# BottomPCB-011713.net
KiCad netlist of a schematic drawn in EAGLE
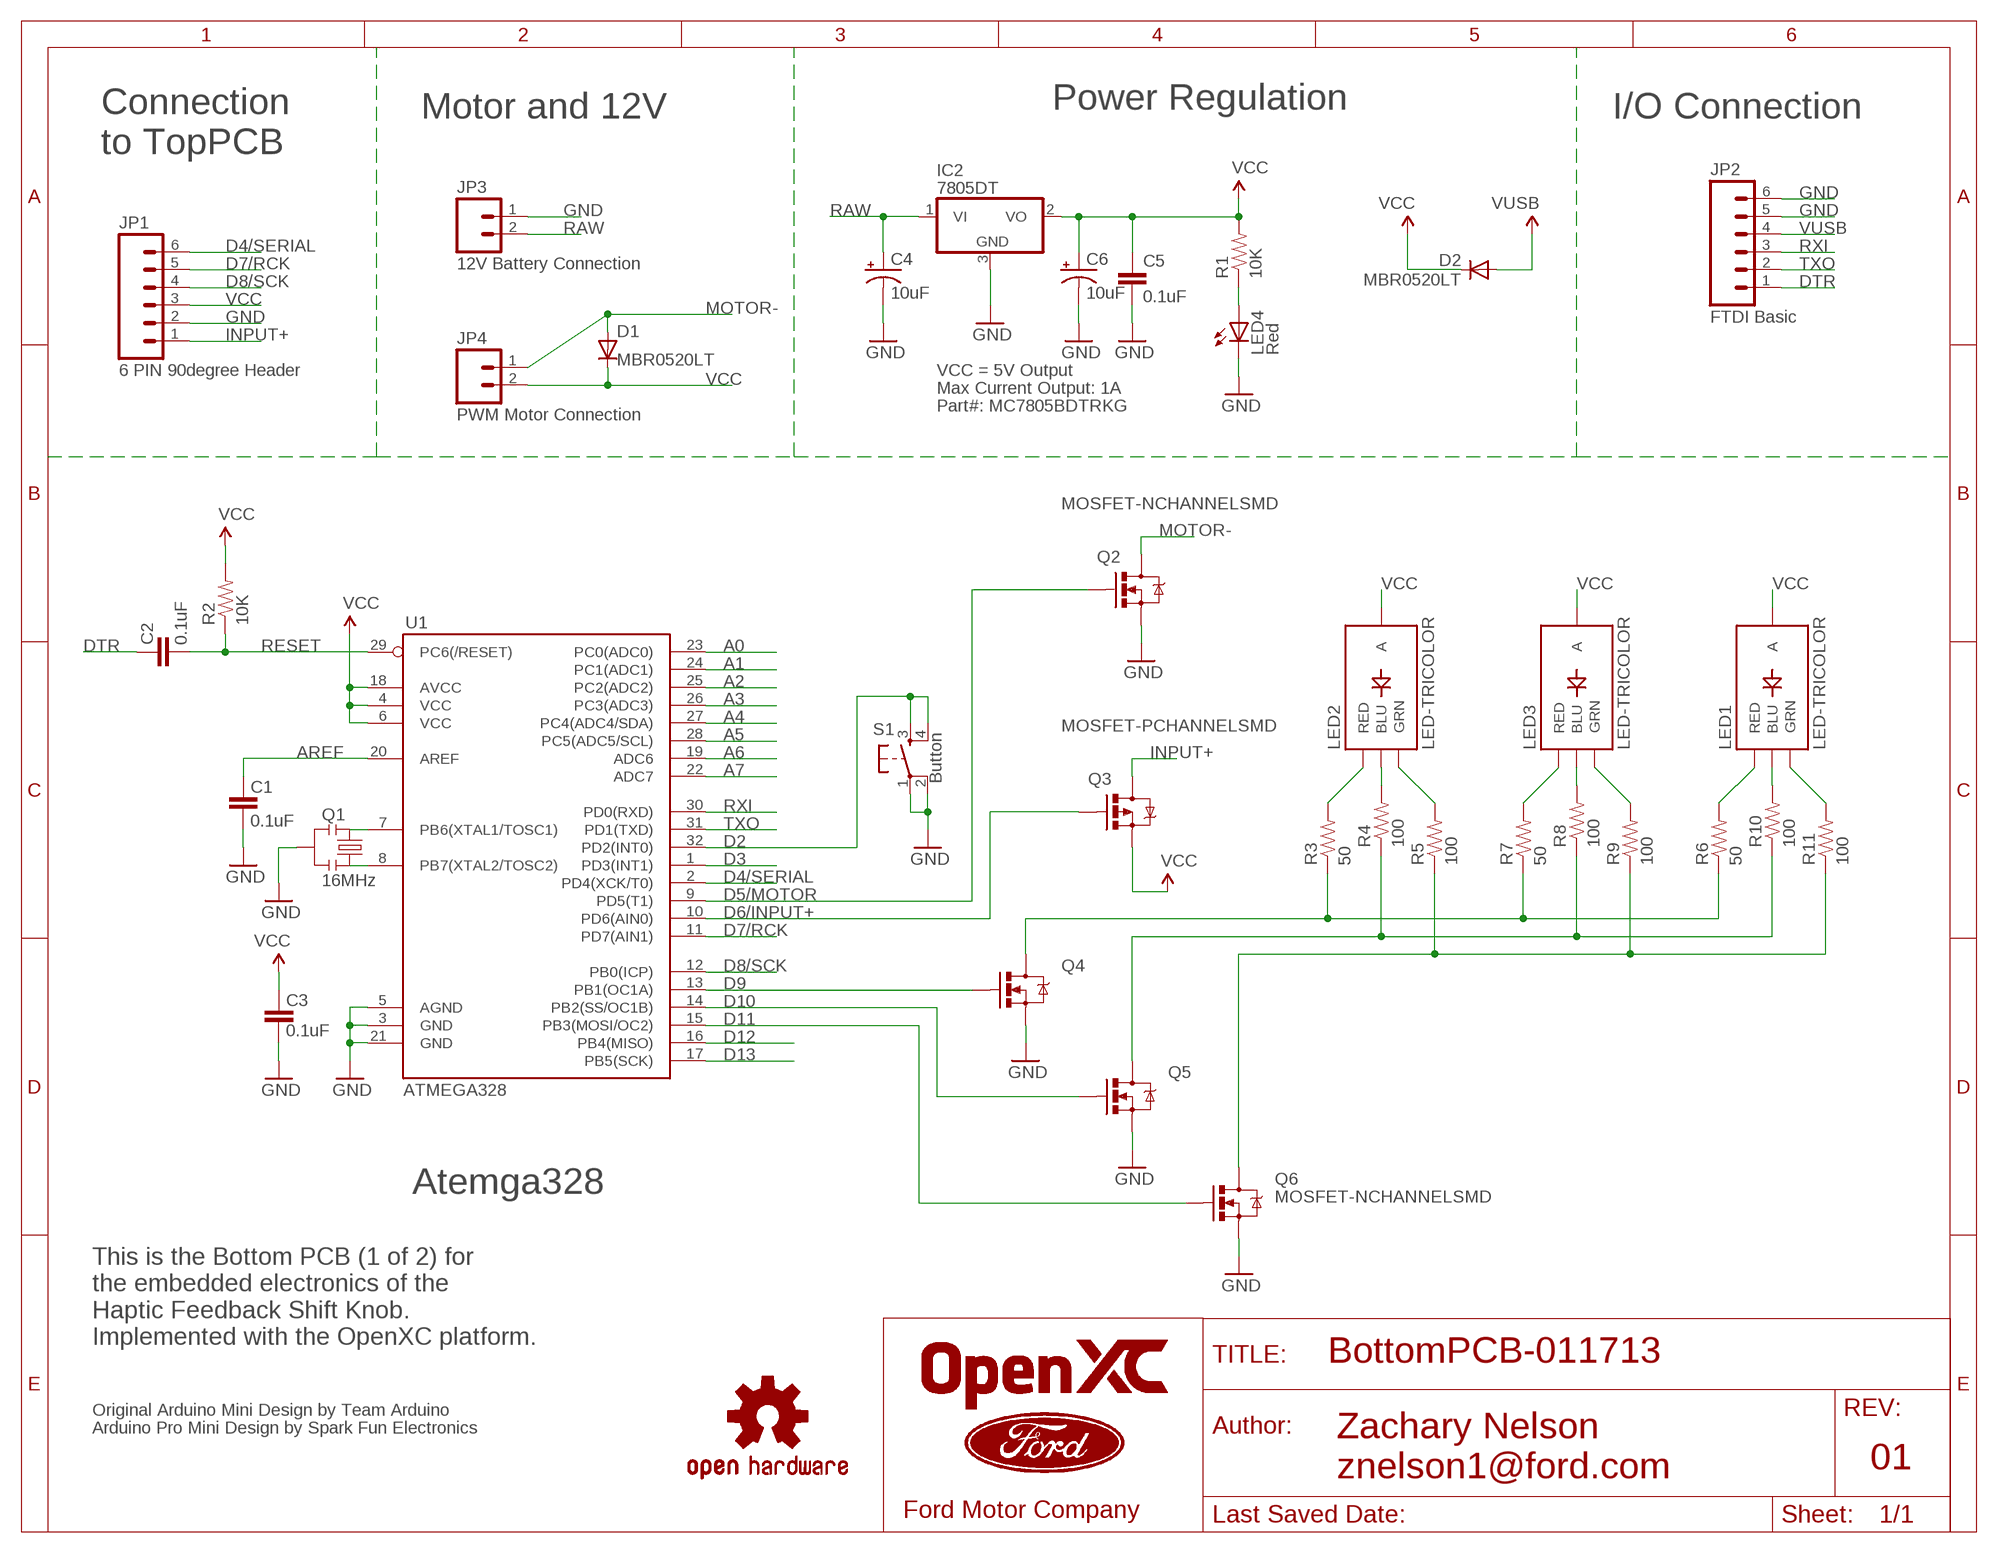
[diagram p0: schematic, sheet 1]

(export (version "E")
  (design (tool "Eeschema 10.0.6"))
  (components
    (comp (ref "C1")
      (value "0.1uF")
      (footprint "eagle-import:0402-CAP")
      (libsource (lib "eagle-import") (part "CAP0402-CAP"))
    )
    (comp (ref "C2")
      (value "0.1uF")
      (footprint "eagle-import:0402-CAP")
      (libsource (lib "eagle-import") (part "CAP0402-CAP"))
    )
    (comp (ref "C3")
      (value "0.1uF")
      (footprint "eagle-import:0402-CAP")
      (libsource (lib "eagle-import") (part "CAP0402-CAP"))
    )
    (comp (ref "C4")
      (value "10uF")
      (footprint "eagle-import:EIA3216")
      (libsource (lib "eagle-import") (part "CAP_POL1206"))
    )
    (comp (ref "C5")
      (value "0.1uF")
      (footprint "eagle-import:0402-CAP")
      (libsource (lib "eagle-import") (part "CAP0402-CAP"))
    )
    (comp (ref "C6")
      (value "10uF")
      (footprint "eagle-import:EIA3216")
      (libsource (lib "eagle-import") (part "CAP_POL1206"))
    )
    (comp (ref "D1")
      (value "MBR0520LT")
      (footprint "eagle-import:SOD123")
      (libsource (lib "eagle-import") (part "MBR0520LT"))
    )
    (comp (ref "D2")
      (value "MBR0520LT")
      (footprint "eagle-import:SOD123")
      (libsource (lib "eagle-import") (part "MBR0520LT"))
    )
    (comp (ref "IC2")
      (value "7805DT")
      (footprint "eagle-import:TO252")
      (libsource (lib "eagle-import") (part "78DT05"))
    )
    (comp (ref "JP1")
      (value "6 PIN 90degree Header")
      (footprint "eagle-import:1X06")
      (libsource (lib "eagle-import") (part "M06SIP"))
    )
    (comp (ref "JP2")
      (value "FTDI Basic")
      (footprint "eagle-import:1X06")
      (libsource (lib "eagle-import") (part "M06SIP"))
    )
    (comp (ref "JP3")
      (value "12V Battery Connection")
      (footprint "eagle-import:JST-2-SMD")
      (fields (field (name "PROD_ID") "CONN-08352"))
      (libsource (lib "eagle-import") (part "M02-JST-2MM-SMT"))
    )
    (comp (ref "JP4")
      (value "PWM Motor Connection")
      (footprint "eagle-import:JST-2-SMD")
      (libsource (lib "eagle-import") (part "M02-JST-2MM-SMT"))
    )
    (comp (ref "LED1")
      (value "LED-TRICOLOR")
      (footprint "eagle-import:LED-TRICOLOR-SMD")
      (libsource (lib "eagle-import") (part "LED-TRICOLOR"))
    )
    (comp (ref "LED2")
      (value "LED-TRICOLOR")
      (footprint "eagle-import:LED-TRICOLOR-SMD")
      (libsource (lib "eagle-import") (part "LED-TRICOLOR"))
    )
    (comp (ref "LED3")
      (value "LED-TRICOLOR")
      (footprint "eagle-import:LED-TRICOLOR-SMD")
      (libsource (lib "eagle-import") (part "LED-TRICOLOR"))
    )
    (comp (ref "LED4")
      (value "Red")
      (footprint "eagle-import:LED-0603")
      (libsource (lib "eagle-import") (part "LED0603"))
    )
    (comp (ref "Q1")
      (value "16MHz")
      (footprint "eagle-import:RESONATOR-SMD")
      (libsource (lib "eagle-import") (part "RESONATORSMD"))
    )
    (comp (ref "Q2")
      (value "MOSFET-NCHANNELSMD")
      (footprint "eagle-import:SOT23-3")
      (libsource (lib "eagle-import") (part "MOSFET-NCHANNELSMD"))
    )
    (comp (ref "Q3")
      (value "MOSFET-PCHANNELSMD")
      (footprint "eagle-import:SOT23-3")
      (libsource (lib "eagle-import") (part "MOSFET-PCHANNELSMD"))
    )
    (comp (ref "Q4")
      (value "MOSFET-NCHANNELSMD")
      (footprint "eagle-import:SOT23-3")
      (libsource (lib "eagle-import") (part "MOSFET-NCHANNELSMD"))
    )
    (comp (ref "Q5")
      (value "MOSFET-NCHANNELSMD")
      (footprint "eagle-import:SOT23-3")
      (libsource (lib "eagle-import") (part "MOSFET-NCHANNELSMD"))
    )
    (comp (ref "Q6")
      (value "MOSFET-NCHANNELSMD")
      (footprint "eagle-import:SOT23-3")
      (libsource (lib "eagle-import") (part "MOSFET-NCHANNELSMD"))
    )
    (comp (ref "R1")
      (value "10K")
      (footprint "eagle-import:0402-RES")
      (libsource (lib "eagle-import") (part "RESISTOR0402-RES"))
    )
    (comp (ref "R2")
      (value "10K")
      (footprint "eagle-import:0402-RES")
      (libsource (lib "eagle-import") (part "RESISTOR0402-RES"))
    )
    (comp (ref "R3")
      (value "50")
      (footprint "eagle-import:0805")
      (libsource (lib "eagle-import") (part "SparkFun-Resistors_RESISTOR0805-RES"))
    )
    (comp (ref "R4")
      (value "100")
      (footprint "eagle-import:0805")
      (libsource (lib "eagle-import") (part "SparkFun-Resistors_RESISTOR0805-RES"))
    )
    (comp (ref "R5")
      (value "100")
      (footprint "eagle-import:0805")
      (libsource (lib "eagle-import") (part "SparkFun-Resistors_RESISTOR0805-RES"))
    )
    (comp (ref "R6")
      (value "50")
      (footprint "eagle-import:0805")
      (libsource (lib "eagle-import") (part "SparkFun-Resistors_RESISTOR0805-RES"))
    )
    (comp (ref "R7")
      (value "50")
      (footprint "eagle-import:0805")
      (libsource (lib "eagle-import") (part "SparkFun-Resistors_RESISTOR0805-RES"))
    )
    (comp (ref "R8")
      (value "100")
      (footprint "eagle-import:0805")
      (libsource (lib "eagle-import") (part "SparkFun-Resistors_RESISTOR0805-RES"))
    )
    (comp (ref "R9")
      (value "100")
      (footprint "eagle-import:0805")
      (libsource (lib "eagle-import") (part "SparkFun-Resistors_RESISTOR0805-RES"))
    )
    (comp (ref "R10")
      (value "100")
      (footprint "eagle-import:0805")
      (libsource (lib "eagle-import") (part "SparkFun-Resistors_RESISTOR0805-RES"))
    )
    (comp (ref "R11")
      (value "100")
      (footprint "eagle-import:0805")
      (libsource (lib "eagle-import") (part "SparkFun-Resistors_RESISTOR0805-RES"))
    )
    (comp (ref "S1")
      (value "Button")
      (footprint "eagle-import:TACTILE_SWITCH_SMD")
      (libsource (lib "eagle-import") (part "TAC_SWITCHSMD"))
    )
    (comp (ref "U$3")
      (value "OSHW-LOGOS")
      (footprint "eagle-import:OSHW-LOGO-S")
      (libsource (lib "eagle-import") (part "OSHW-LOGOS"))
    )
    (comp (ref "U1")
      (value "ATMEGA328")
      (footprint "eagle-import:TQFP32-08")
      (libsource (lib "eagle-import") (part "ATMEGA168"))
    )
  )
  (nets
    (net (code "1") (name "/A0") (class "Default")
      (node (ref "U1") (pin "23") (pinfunction "PC0(ADC0)_23") (pintype "bidirectional"))
    )
    (net (code "2") (name "/A1") (class "Default")
      (node (ref "U1") (pin "24") (pinfunction "PC1(ADC1)_24") (pintype "bidirectional"))
    )
    (net (code "3") (name "/A2") (class "Default")
      (node (ref "U1") (pin "25") (pinfunction "PC2(ADC2)_25") (pintype "bidirectional"))
    )
    (net (code "4") (name "/A3") (class "Default")
      (node (ref "U1") (pin "26") (pinfunction "PC3(ADC3)_26") (pintype "bidirectional"))
    )
    (net (code "5") (name "/A4") (class "Default")
      (node (ref "U1") (pin "27") (pinfunction "PC4(ADC4/SDA)_27") (pintype "bidirectional"))
    )
    (net (code "6") (name "/A5") (class "Default")
      (node (ref "U1") (pin "28") (pinfunction "PC5(ADC5/SCL)_28") (pintype "bidirectional"))
    )
    (net (code "7") (name "/A6") (class "Default")
      (node (ref "U1") (pin "19") (pinfunction "ADC6_19") (pintype "bidirectional"))
    )
    (net (code "8") (name "/A7") (class "Default")
      (node (ref "U1") (pin "22") (pinfunction "ADC7_22") (pintype "bidirectional"))
    )
    (net (code "9") (name "/AREF") (class "Default")
      (node (ref "C1") (pin "2") (pinfunction "2_2") (pintype "passive"))
      (node (ref "U1") (pin "20") (pinfunction "AREF_20") (pintype "bidirectional"))
    )
    (net (code "10") (name "/D2") (class "Default")
      (node (ref "S1") (pin "3") (pinfunction "3_3") (pintype "passive"))
      (node (ref "S1") (pin "4") (pinfunction "4_4") (pintype "passive"))
      (node (ref "U1") (pin "32") (pinfunction "PD2(INT0)_32") (pintype "bidirectional"))
    )
    (net (code "11") (name "/D3") (class "Default")
      (node (ref "U1") (pin "1") (pinfunction "PD3(INT1)_1") (pintype "bidirectional"))
    )
    (net (code "12") (name "/D4{slash}SERIAL") (class "Default")
      (node (ref "JP1") (pin "6") (pinfunction "6_6") (pintype "passive"))
      (node (ref "U1") (pin "2") (pinfunction "PD4(XCK/T0)_2") (pintype "bidirectional"))
    )
    (net (code "13") (name "/D5{slash}MOTOR") (class "Default")
      (node (ref "Q2") (pin "1") (pinfunction "G_1") (pintype "passive"))
      (node (ref "U1") (pin "9") (pinfunction "PD5(T1)_9") (pintype "bidirectional"))
    )
    (net (code "14") (name "/D6{slash}INPUT+") (class "Default")
      (node (ref "Q3") (pin "1") (pinfunction "G_1") (pintype "passive"))
      (node (ref "U1") (pin "10") (pinfunction "PD6(AIN0)_10") (pintype "bidirectional"))
    )
    (net (code "15") (name "/D7{slash}RCK") (class "Default")
      (node (ref "JP1") (pin "5") (pinfunction "5_5") (pintype "passive"))
      (node (ref "U1") (pin "11") (pinfunction "PD7(AIN1)_11") (pintype "bidirectional"))
    )
    (net (code "16") (name "/D8{slash}SCK") (class "Default")
      (node (ref "JP1") (pin "4") (pinfunction "4_4") (pintype "passive"))
      (node (ref "U1") (pin "12") (pinfunction "PB0(ICP)_12") (pintype "bidirectional"))
    )
    (net (code "17") (name "/D9") (class "Default")
      (node (ref "Q4") (pin "3") (pinfunction "D_3") (pintype "passive"))
      (node (ref "R3") (pin "1") (pinfunction "1_1") (pintype "passive"))
      (node (ref "R6") (pin "1") (pinfunction "1_1") (pintype "passive"))
      (node (ref "R7") (pin "1") (pinfunction "1_1") (pintype "passive"))
    )
    (net (code "18") (name "/D10") (class "Default")
      (node (ref "Q5") (pin "3") (pinfunction "D_3") (pintype "passive"))
      (node (ref "R10") (pin "1") (pinfunction "1_1") (pintype "passive"))
      (node (ref "R4") (pin "1") (pinfunction "1_1") (pintype "passive"))
      (node (ref "R8") (pin "1") (pinfunction "1_1") (pintype "passive"))
    )
    (net (code "19") (name "/D11") (class "Default")
      (node (ref "Q6") (pin "3") (pinfunction "D_3") (pintype "passive"))
      (node (ref "R11") (pin "1") (pinfunction "1_1") (pintype "passive"))
      (node (ref "R5") (pin "1") (pinfunction "1_1") (pintype "passive"))
      (node (ref "R9") (pin "1") (pinfunction "1_1") (pintype "passive"))
    )
    (net (code "20") (name "/D12") (class "Default")
      (node (ref "U1") (pin "16") (pinfunction "PB4(MISO)_16") (pintype "bidirectional"))
    )
    (net (code "21") (name "/D13") (class "Default")
      (node (ref "U1") (pin "17") (pinfunction "PB5(SCK)_17") (pintype "bidirectional"))
    )
    (net (code "22") (name "/DTR") (class "Default")
      (node (ref "C2") (pin "2") (pinfunction "2_2") (pintype "passive"))
      (node (ref "JP2") (pin "1") (pinfunction "1_1") (pintype "passive"))
    )
    (net (code "23") (name "/INPUT+") (class "Default")
      (node (ref "JP1") (pin "1") (pinfunction "1_1") (pintype "passive"))
      (node (ref "Q3") (pin "3") (pinfunction "D_3") (pintype "passive"))
    )
    (net (code "24") (name "/MOTOR-") (class "Default")
      (node (ref "D1") (pin "A") (pinfunction "A_A") (pintype "passive"))
      (node (ref "JP4") (pin "1") (pinfunction "2_1") (pintype "passive"))
      (node (ref "Q2") (pin "3") (pinfunction "D_3") (pintype "passive"))
    )
    (net (code "25") (name "/RAW") (class "Default")
      (node (ref "C4") (pin "A") (pinfunction "+_A") (pintype "passive"))
      (node (ref "IC2") (pin "1") (pinfunction "VI_1") (pintype "input"))
      (node (ref "JP3") (pin "2") (pinfunction "1_2") (pintype "passive"))
    )
    (net (code "26") (name "/RESET") (class "Default")
      (node (ref "C2") (pin "1") (pinfunction "1_1") (pintype "passive"))
      (node (ref "R2") (pin "1") (pinfunction "1_1") (pintype "passive"))
      (node (ref "U1") (pin "29") (pinfunction "PC6(/RESET)_29") (pintype "bidirectional"))
    )
    (net (code "27") (name "/RXI") (class "Default")
      (node (ref "JP2") (pin "3") (pinfunction "3_3") (pintype "passive"))
      (node (ref "U1") (pin "30") (pinfunction "PD0(RXD)_30") (pintype "bidirectional"))
    )
    (net (code "28") (name "/TXO") (class "Default")
      (node (ref "JP2") (pin "2") (pinfunction "2_2") (pintype "passive"))
      (node (ref "U1") (pin "31") (pinfunction "PD1(TXD)_31") (pintype "bidirectional"))
    )
    (net (code "29") (name "GND") (class "Default")
      (node (ref "C1") (pin "1") (pinfunction "1_1") (pintype "passive"))
      (node (ref "C3") (pin "1") (pinfunction "1_1") (pintype "passive"))
      (node (ref "C4") (pin "C") (pinfunction "-_C") (pintype "passive"))
      (node (ref "C5") (pin "2") (pinfunction "2_2") (pintype "passive"))
      (node (ref "C6") (pin "C") (pinfunction "-_C") (pintype "passive"))
      (node (ref "IC2") (pin "3") (pinfunction "GND_3") (pintype "passive"))
      (node (ref "JP1") (pin "2") (pinfunction "2_2") (pintype "passive"))
      (node (ref "JP2") (pin "5") (pinfunction "5_5") (pintype "passive"))
      (node (ref "JP2") (pin "6") (pinfunction "6_6") (pintype "passive"))
      (node (ref "JP3") (pin "1") (pinfunction "2_1") (pintype "passive"))
      (node (ref "LED4") (pin "C") (pinfunction "C_C") (pintype "passive"))
      (node (ref "Q1") (pin "2") (pinfunction "2_2") (pintype "passive"))
      (node (ref "Q2") (pin "2") (pinfunction "S_2") (pintype "passive"))
      (node (ref "Q4") (pin "2") (pinfunction "S_2") (pintype "passive"))
      (node (ref "Q5") (pin "2") (pinfunction "S_2") (pintype "passive"))
      (node (ref "Q6") (pin "2") (pinfunction "S_2") (pintype "passive"))
      (node (ref "S1") (pin "1") (pinfunction "1_1") (pintype "passive"))
      (node (ref "S1") (pin "2") (pinfunction "2_2") (pintype "passive"))
      (node (ref "U1") (pin "21") (pinfunction "GND_21") (pintype "bidirectional"))
      (node (ref "U1") (pin "3") (pinfunction "GND_3") (pintype "bidirectional"))
      (node (ref "U1") (pin "5") (pinfunction "AGND_5") (pintype "bidirectional"))
    )
    (net (code "30") (name "Net-(LED1-BLU)") (class "Default")
      (node (ref "LED1") (pin "B") (pinfunction "BLU_B") (pintype "bidirectional"))
      (node (ref "R10") (pin "2") (pinfunction "2_2") (pintype "passive"))
    )
    (net (code "31") (name "Net-(LED1-GRN)") (class "Default")
      (node (ref "LED1") (pin "G") (pinfunction "GRN_G") (pintype "bidirectional"))
      (node (ref "R11") (pin "2") (pinfunction "2_2") (pintype "passive"))
    )
    (net (code "32") (name "Net-(LED1-RED)") (class "Default")
      (node (ref "LED1") (pin "R") (pinfunction "RED_R") (pintype "bidirectional"))
      (node (ref "R6") (pin "2") (pinfunction "2_2") (pintype "passive"))
    )
    (net (code "33") (name "Net-(LED2-BLU)") (class "Default")
      (node (ref "LED2") (pin "B") (pinfunction "BLU_B") (pintype "bidirectional"))
      (node (ref "R4") (pin "2") (pinfunction "2_2") (pintype "passive"))
    )
    (net (code "34") (name "Net-(LED2-GRN)") (class "Default")
      (node (ref "LED2") (pin "G") (pinfunction "GRN_G") (pintype "bidirectional"))
      (node (ref "R5") (pin "2") (pinfunction "2_2") (pintype "passive"))
    )
    (net (code "35") (name "Net-(LED2-RED)") (class "Default")
      (node (ref "LED2") (pin "R") (pinfunction "RED_R") (pintype "bidirectional"))
      (node (ref "R3") (pin "2") (pinfunction "2_2") (pintype "passive"))
    )
    (net (code "36") (name "Net-(LED3-BLU)") (class "Default")
      (node (ref "LED3") (pin "B") (pinfunction "BLU_B") (pintype "bidirectional"))
      (node (ref "R8") (pin "2") (pinfunction "2_2") (pintype "passive"))
    )
    (net (code "37") (name "Net-(LED3-GRN)") (class "Default")
      (node (ref "LED3") (pin "G") (pinfunction "GRN_G") (pintype "bidirectional"))
      (node (ref "R9") (pin "2") (pinfunction "2_2") (pintype "passive"))
    )
    (net (code "38") (name "Net-(LED3-RED)") (class "Default")
      (node (ref "LED3") (pin "R") (pinfunction "RED_R") (pintype "bidirectional"))
      (node (ref "R7") (pin "2") (pinfunction "2_2") (pintype "passive"))
    )
    (net (code "39") (name "Net-(LED4-PadA)") (class "Default")
      (node (ref "LED4") (pin "A") (pinfunction "A_A") (pintype "passive"))
      (node (ref "R1") (pin "1") (pinfunction "1_1") (pintype "passive"))
    )
    (net (code "40") (name "Net-(Q4-G)") (class "Default")
      (node (ref "Q4") (pin "1") (pinfunction "G_1") (pintype "passive"))
      (node (ref "U1") (pin "13") (pinfunction "PB1(OC1A)_13") (pintype "bidirectional"))
    )
    (net (code "41") (name "Net-(Q5-G)") (class "Default")
      (node (ref "Q5") (pin "1") (pinfunction "G_1") (pintype "passive"))
      (node (ref "U1") (pin "14") (pinfunction "PB2(SS/OC1B)_14") (pintype "bidirectional"))
    )
    (net (code "42") (name "Net-(Q6-G)") (class "Default")
      (node (ref "Q6") (pin "1") (pinfunction "G_1") (pintype "passive"))
      (node (ref "U1") (pin "15") (pinfunction "PB3(MOSI/OC2)_15") (pintype "bidirectional"))
    )
    (net (code "43") (name "Net-(U1-PB6(XTAL1{slash}TOSC1))") (class "Default")
      (node (ref "Q1") (pin "3") (pinfunction "3_3") (pintype "passive"))
      (node (ref "U1") (pin "7") (pinfunction "PB6(XTAL1/TOSC1)_7") (pintype "bidirectional"))
    )
    (net (code "44") (name "Net-(U1-PB7(XTAL2{slash}TOSC2))") (class "Default")
      (node (ref "Q1") (pin "1") (pinfunction "1_1") (pintype "passive"))
      (node (ref "U1") (pin "8") (pinfunction "PB7(XTAL2/TOSC2)_8") (pintype "bidirectional"))
    )
    (net (code "45") (name "VCC") (class "Default")
      (node (ref "C3") (pin "2") (pinfunction "2_2") (pintype "passive"))
      (node (ref "C5") (pin "1") (pinfunction "1_1") (pintype "passive"))
      (node (ref "C6") (pin "A") (pinfunction "+_A") (pintype "passive"))
      (node (ref "D1") (pin "C") (pinfunction "C_C") (pintype "passive"))
      (node (ref "D2") (pin "C") (pinfunction "C_C") (pintype "passive"))
      (node (ref "IC2") (pin "2") (pinfunction "VO_2") (pintype "passive"))
      (node (ref "JP1") (pin "3") (pinfunction "3_3") (pintype "passive"))
      (node (ref "JP4") (pin "2") (pinfunction "1_2") (pintype "passive"))
      (node (ref "LED1") (pin "A") (pinfunction "A_A") (pintype "bidirectional"))
      (node (ref "LED2") (pin "A") (pinfunction "A_A") (pintype "bidirectional"))
      (node (ref "LED3") (pin "A") (pinfunction "A_A") (pintype "bidirectional"))
      (node (ref "Q3") (pin "2") (pinfunction "S_2") (pintype "passive"))
      (node (ref "R1") (pin "2") (pinfunction "2_2") (pintype "passive"))
      (node (ref "R2") (pin "2") (pinfunction "2_2") (pintype "passive"))
      (node (ref "U1") (pin "18") (pinfunction "AVCC_18") (pintype "bidirectional"))
      (node (ref "U1") (pin "4") (pinfunction "VCC_4") (pintype "bidirectional"))
      (node (ref "U1") (pin "6") (pinfunction "VCC_6") (pintype "bidirectional"))
    )
    (net (code "46") (name "VUSB") (class "Default")
      (node (ref "D2") (pin "A") (pinfunction "A_A") (pintype "passive"))
      (node (ref "JP2") (pin "4") (pinfunction "4_4") (pintype "passive"))
    )
  )
)
